# KeyBoard.net
KiCad netlist of a schematic drawn in Altium Designer
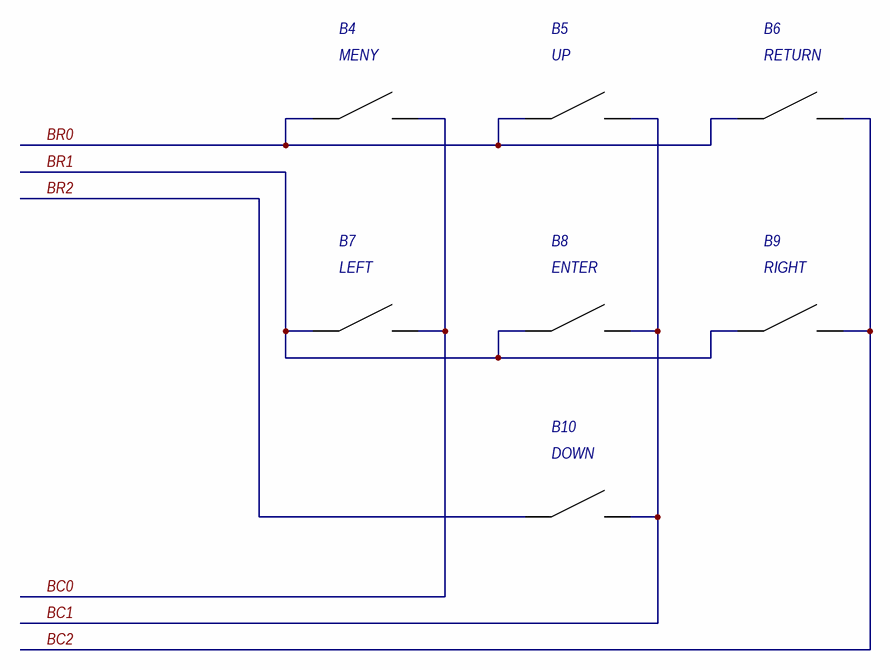
[diagram p0: KeyBoard.SchDoc]

(export (version "E")
  (design (tool "Eeschema 10.0.6"))
  (components
    (comp (ref "B4") (value "MENY") (footprint "BUTTON_DIP") (libsource (lib "my_lib") (part "BUTTON")))
    (comp (ref "B5") (value "UP") (footprint "BUTTON_DIP") (libsource (lib "my_lib") (part "BUTTON")))
    (comp (ref "B6") (value "RETURN") (footprint "BUTTON_DIP") (libsource (lib "my_lib") (part "BUTTON")))
    (comp (ref "B7") (value "LEFT") (footprint "BUTTON_DIP") (libsource (lib "my_lib") (part "BUTTON")))
    (comp (ref "B8") (value "ENTER") (footprint "BUTTON_DIP") (libsource (lib "my_lib") (part "BUTTON")))
    (comp (ref "B9") (value "RIGHT") (footprint "BUTTON_DIP") (libsource (lib "my_lib") (part "BUTTON")))
    (comp (ref "B10") (value "DOWN") (footprint "BUTTON_DIP") (libsource (lib "my_lib") (part "BUTTON")))
  )
  (nets
    (net (code "1") (name "/BC0") (class "Default")
      (node (ref "B4") (pin "2") (pinfunction "2_2") (pintype "passive"))
      (node (ref "B7") (pin "2") (pinfunction "2_2") (pintype "passive"))
    )
    (net (code "2") (name "/BC1") (class "Default")
      (node (ref "B10") (pin "2") (pinfunction "2_2") (pintype "passive"))
      (node (ref "B5") (pin "2") (pinfunction "2_2") (pintype "passive"))
      (node (ref "B8") (pin "2") (pinfunction "2_2") (pintype "passive"))
    )
    (net (code "3") (name "/BC2") (class "Default")
      (node (ref "B6") (pin "2") (pinfunction "2_2") (pintype "passive"))
      (node (ref "B9") (pin "2") (pinfunction "2_2") (pintype "passive"))
    )
    (net (code "4") (name "/BR0") (class "Default")
      (node (ref "B4") (pin "1") (pinfunction "1_1") (pintype "passive"))
      (node (ref "B5") (pin "1") (pinfunction "1_1") (pintype "passive"))
      (node (ref "B6") (pin "1") (pinfunction "1_1") (pintype "passive"))
    )
    (net (code "5") (name "/BR1") (class "Default")
      (node (ref "B7") (pin "1") (pinfunction "1_1") (pintype "passive"))
      (node (ref "B8") (pin "1") (pinfunction "1_1") (pintype "passive"))
      (node (ref "B9") (pin "1") (pinfunction "1_1") (pintype "passive"))
    )
    (net (code "6") (name "/BR2") (class "Default")
      (node (ref "B10") (pin "1") (pinfunction "1_1") (pintype "passive"))
    )
  )
)
